# TPS612997YBHR_3_6V_lowIQ_1_9A.net
KiCad netlist of a schematic drawn in Altium Designer
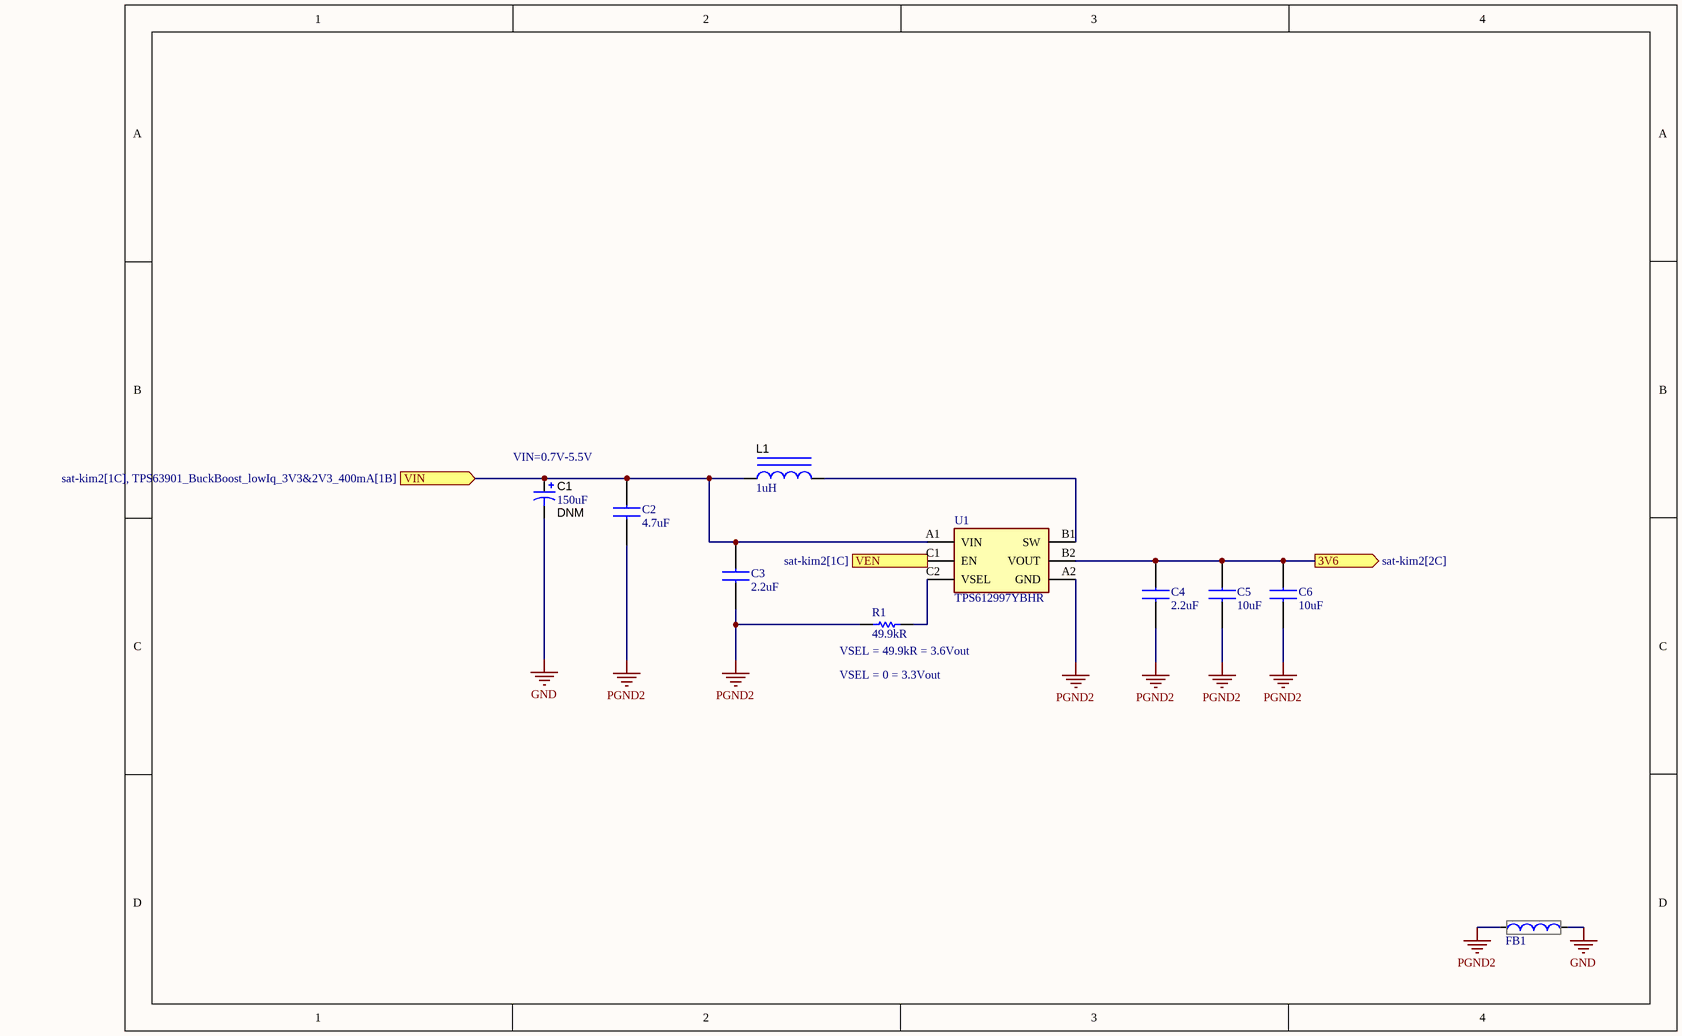
[diagram p0: TPS612997YBHR_3.6V_lowIQ_1.9A.SchDoc]

(export (version "E")
  (design (tool "Eeschema 10.0.6"))
  (components
    (comp (ref "C1")
      (value "DNM")
      (footprint "7343-31")
      (description "Tantalum Capacitors - Solid SMD 10V 150uF 2917 10% ESR=100mOhms")
      (fields
        (field (name "PARTNUMBER") "T495D157K010ATE100")
        (field (name "MANUFACTURER") "Kemet")
        (field (name "VALUEDISPLAYED") "150uF")
        (field (name "PUBLISHER") "Texas Instruments")
      )
      (libsource (lib "stm32wl-dev") (part "T495D157K010ATE100"))
    )
    (comp (ref "C2")
      (value "4.7uF")
      (footprint "CAPC1608X90N")
      (description "Multilayer Ceramic Capacitors MLCC - SMD/SMT 4.7 uF 10 VDC 20% 0603 X7R")
      (fields
        (field (name "MANUFACTURER_PART_NUMBER") "GRM188Z71A475ME15D")
        (field (name "MOUSER PART NUMBER") "81-GRM188Z71A475ME5D")
      )
      (libsource (lib "stm32wl-dev") (part "GRM188Z71A475ME15D"))
    )
    (comp (ref "C3")
      (value "2.2uF")
      (footprint "stm32wl-dev:CAPC1005X70N")
      (description "Multilayer Ceramic Capacitors MLCC - SMD/SMT 2.2 uF 10 VDC 20% 0402 X5R")
      (fields
        (field (name "MANUFACTURER_PART_NUMBER") "GRM155R61A225ME95D")
        (field (name "MOUSER PART NUMBER") "81-GRM155R61A225ME5D")
      )
      (libsource (lib "stm32wl-dev") (part "GRM155R61A225ME95D"))
    )
    (comp (ref "C4")
      (value "2.2uF")
      (footprint "stm32wl-dev:CAPC1005X70N")
      (description "Multilayer Ceramic Capacitors MLCC - SMD/SMT 2.2 uF 10 VDC 20% 0402 X5R")
      (fields
        (field (name "MANUFACTURER_PART_NUMBER") "GRM155R61A225ME95D")
        (field (name "MOUSER PART NUMBER") "81-GRM155R61A225ME5D")
      )
      (libsource (lib "stm32wl-dev") (part "GRM155R61A225ME95D"))
    )
    (comp (ref "C5")
      (value "10uF")
      (footprint "CAPC1005X55N")
      (description "Multilayer Ceramic Capacitors MLCC - SMD/SMT 10 uF 10 VDC 20% 0402 X5R")
      (fields
        (field (name "MANUFACTURER_PART_NUMBER") "GRM155R61A106ME11D")
        (field (name "MOUSER PART NUMBER") "81-GRM155R61A106ME1D")
      )
      (libsource (lib "stm32wl-dev") (part "GRM155R61A106ME11D"))
    )
    (comp (ref "C6")
      (value "10uF")
      (footprint "CAPC1005X55N")
      (description "Multilayer Ceramic Capacitors MLCC - SMD/SMT 10 uF 10 VDC 20% 0402 X5R")
      (fields
        (field (name "MANUFACTURER_PART_NUMBER") "GRM155R61A106ME11D")
        (field (name "MOUSER PART NUMBER") "81-GRM155R61A106ME1D")
      )
      (libsource (lib "stm32wl-dev") (part "GRM155R61A106ME11D"))
    )
    (comp (ref "FB1")
      (value "BLM18AG102SN1D")
      (footprint "stm32wl-dev:BLM18SP221SN1B")
      (description "Ferrite Bead - 1000 OHM 25%")
      (fields (field (name "MOUSER PART NUMBER") "81-BLM11A102S"))
      (libsource (lib "stm32wl-dev") (part "BLM18AG102SN1D"))
    )
    (comp (ref "L1")
      (value "XEL4020-102MEB")
      (footprint "XEL4020")
      (description "Power Inductors - SMD 1uH Shld 20% 9.6A 14.6mOhms AECQ2")
      (fields (field (name "MANUFACTURER") "Coilcraft") (field (name "VALUEDISPLAYED") "1uH"))
      (libsource (lib "stm32wl-dev") (part "XEL4020-102MEC"))
    )
    (comp (ref "R1")
      (value "49.9kR")
      (footprint "stm32wl-dev:RESC1005X40N")
      (description "Thick Film Resistors - SMD 1/16watt 49.9Kohms 1%")
      (fields
        (field (name "MANUFACTURER_PART_NUMBER") "CRCW040249K9FKED")
        (field (name "MOUSER PART NUMBER") "71-CRCW0402-49.9K-E3")
      )
      (libsource (lib "stm32wl-dev") (part "CRCW040249K9FKED"))
    )
    (comp (ref "U1")
      (value "TPS612997YBHR")
      (footprint "stm32wl-dev:BGA6C40P2X3_84X123X40")
      (description "Switching Voltage Regulators 95-nA low IQ 5.5-V b oost converter with INLIMIT (1.9A)")
      (fields (field (name "MOUSER PART NUMBER") "595-TPS612997YBHR"))
      (libsource (lib "stm32wl-dev") (part "TPS612997YBHR"))
    )
  )
  (nets
    (net (code "1") (name "/3V6") (class "Default")
      (node (ref "C4") (pin "2") (pinfunction "2_2") (pintype "passive"))
      (node (ref "C5") (pin "2") (pinfunction "2_2") (pintype "passive"))
      (node (ref "C6") (pin "2") (pinfunction "2_2") (pintype "passive"))
      (node (ref "U1") (pin "B2") (pinfunction "VOUT_B2") (pintype "passive"))
    )
    (net (code "2") (name "/VEN") (class "Default")
      (node (ref "U1") (pin "C1") (pinfunction "EN_C1") (pintype "passive"))
    )
    (net (code "3") (name "/VIN") (class "Default")
      (node (ref "C1") (pin "1") (pinfunction "+_1") (pintype "passive"))
      (node (ref "C2") (pin "1") (pinfunction "1_1") (pintype "passive"))
      (node (ref "C3") (pin "2") (pinfunction "2_2") (pintype "passive"))
      (node (ref "L1") (pin "1") (pinfunction "1_1") (pintype "passive"))
      (node (ref "U1") (pin "A1") (pinfunction "VIN_A1") (pintype "passive"))
    )
    (net (code "4") (name "GND") (class "Default")
      (node (ref "C1") (pin "2") (pinfunction "-_2") (pintype "passive"))
      (node (ref "FB1") (pin "2") (pinfunction "2_2") (pintype "passive"))
    )
    (net (code "5") (name "Net-(U1-SW)") (class "Default")
      (node (ref "L1") (pin "2") (pinfunction "2_2") (pintype "passive"))
      (node (ref "U1") (pin "B1") (pinfunction "SW_B1") (pintype "passive"))
    )
    (net (code "6") (name "Net-(U1-VSEL)") (class "Default")
      (node (ref "R1") (pin "1") (pinfunction "1_1") (pintype "passive"))
      (node (ref "U1") (pin "C2") (pinfunction "VSEL_C2") (pintype "passive"))
    )
    (net (code "7") (name "PGND2") (class "Default")
      (node (ref "C2") (pin "2") (pinfunction "2_2") (pintype "passive"))
      (node (ref "C3") (pin "1") (pinfunction "1_1") (pintype "passive"))
      (node (ref "C4") (pin "1") (pinfunction "1_1") (pintype "passive"))
      (node (ref "C5") (pin "1") (pinfunction "1_1") (pintype "passive"))
      (node (ref "C6") (pin "1") (pinfunction "1_1") (pintype "passive"))
      (node (ref "FB1") (pin "1") (pinfunction "1_1") (pintype "passive"))
      (node (ref "R1") (pin "2") (pinfunction "2_2") (pintype "passive"))
      (node (ref "U1") (pin "A2") (pinfunction "GND_A2") (pintype "passive"))
    )
  )
)
